# start_board.net
KiCad netlist of a schematic drawn in EAGLE
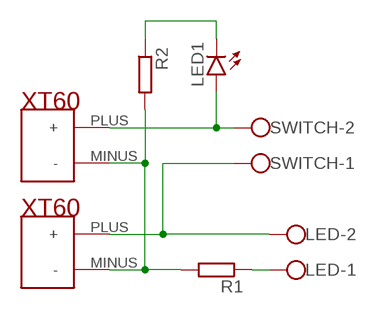
[diagram p0: schematic, sheet 1]

(export (version "E")
  (design (tool "Eeschema 10.0.6"))
  (components
    (comp (ref "LED")
      (value "W237-102")
      (footprint "eagle-import:W237-102")
      (fields (field (name "MPN") "237-102"))
      (libsource (lib "eagle-import") (part "W237-102"))
    )
    (comp (ref "LED1")
      (value "LEDCHIPLED_1206")
      (footprint "eagle-import:CHIPLED_1206")
      (libsource (lib "eagle-import") (part "LEDCHIPLED_1206"))
    )
    (comp (ref "R1")
      (value "R-EU_M1206")
      (footprint "eagle-import:M1206")
      (libsource (lib "eagle-import") (part "R-EU_M1206"))
    )
    (comp (ref "R2")
      (value "R-EU_M1206")
      (footprint "eagle-import:M1206")
      (libsource (lib "eagle-import") (part "R-EU_M1206"))
    )
    (comp (ref "SWITCH")
      (value "W237-102")
      (footprint "eagle-import:W237-102")
      (fields (field (name "MPN") "237-102"))
      (libsource (lib "eagle-import") (part "W237-102"))
    )
    (comp (ref "U$1")
      (value "XT60")
      (footprint "eagle-import:XT60_FOOTPRINT")
      (libsource (lib "eagle-import") (part "XT60"))
    )
    (comp (ref "U$2")
      (value "XT60")
      (footprint "eagle-import:XT60_FOOTPRINT")
      (libsource (lib "eagle-import") (part "XT60"))
    )
  )
  (nets
    (net (code "1") (name "Net-(LED1-PadC)") (class "Default")
      (node (ref "LED1") (pin "C") (pinfunction "C_C") (pintype "passive"))
      (node (ref "R2") (pin "1") (pinfunction "1_1") (pintype "passive"))
    )
    (net (code "2") (name "Net-(LEDA-KL)") (class "Default")
      (node (ref "LED") (pin "1") (pinfunction "KL_1") (pintype "passive"))
      (node (ref "R1") (pin "1") (pinfunction "1_1") (pintype "passive"))
    )
    (net (code "3") (name "Net-(LEDB-KL)") (class "Default")
      (node (ref "LED") (pin "2") (pinfunction "KL_2") (pintype "passive"))
      (node (ref "SWITCH") (pin "1") (pinfunction "KL_1") (pintype "passive"))
      (node (ref "U$2") (pin "PLUS") (pinfunction "+_PLUS") (pintype "bidirectional"))
    )
    (net (code "4") (name "Net-(SWITCHB-KL)") (class "Default")
      (node (ref "LED1") (pin "A") (pinfunction "A_A") (pintype "passive"))
      (node (ref "SWITCH") (pin "2") (pinfunction "KL_2") (pintype "passive"))
      (node (ref "U$1") (pin "PLUS") (pinfunction "+_PLUS") (pintype "bidirectional"))
    )
    (net (code "5") (name "Net-(U$1--)") (class "Default")
      (node (ref "R1") (pin "2") (pinfunction "2_2") (pintype "passive"))
      (node (ref "R2") (pin "2") (pinfunction "2_2") (pintype "passive"))
      (node (ref "U$1") (pin "MINUS") (pinfunction "-_MINUS") (pintype "bidirectional"))
      (node (ref "U$2") (pin "MINUS") (pinfunction "-_MINUS") (pintype "bidirectional"))
    )
  )
)
